# MCU_and_Output_Connectors.net
KiCad netlist of a schematic drawn in Altium Designer
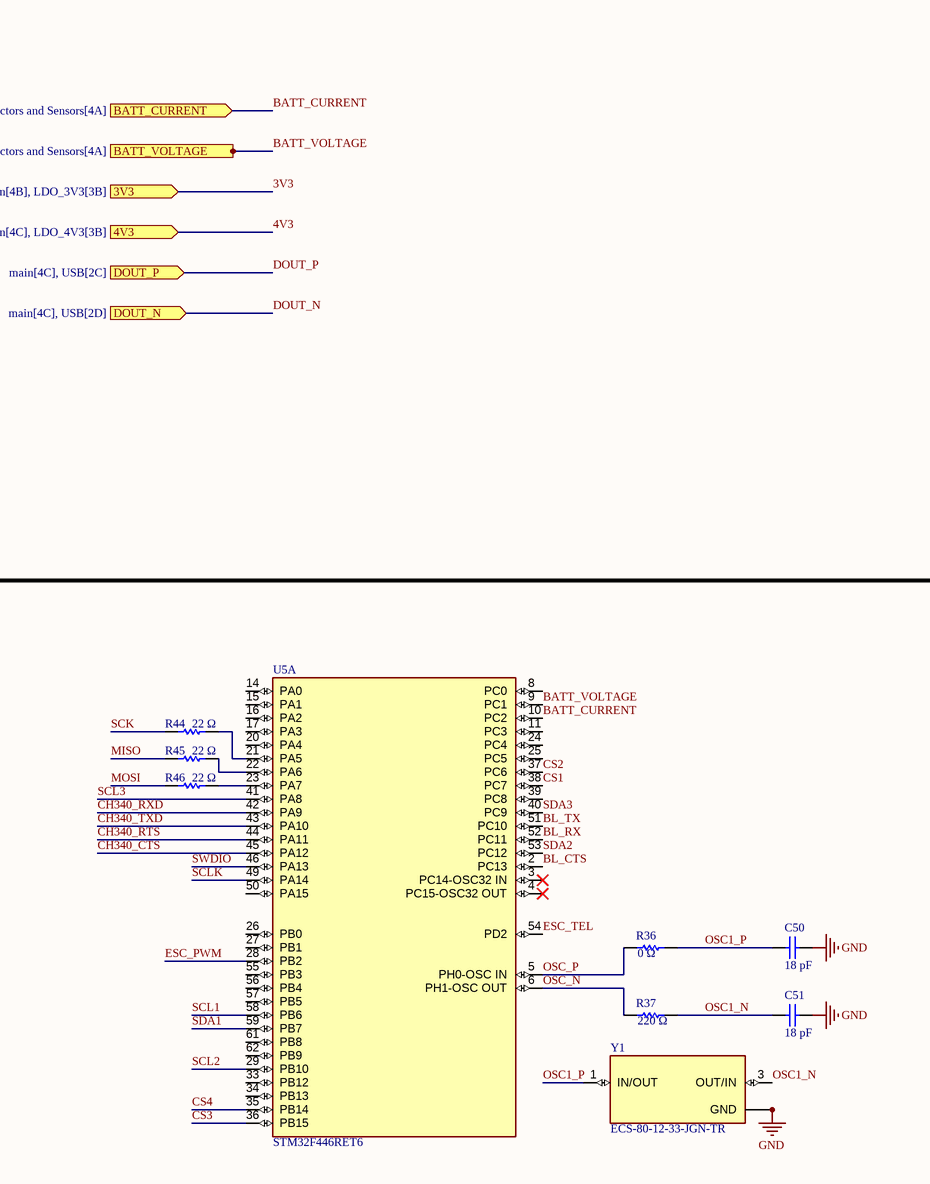
[diagram p0: MCU and Output Connectors.SchDoc, top left]
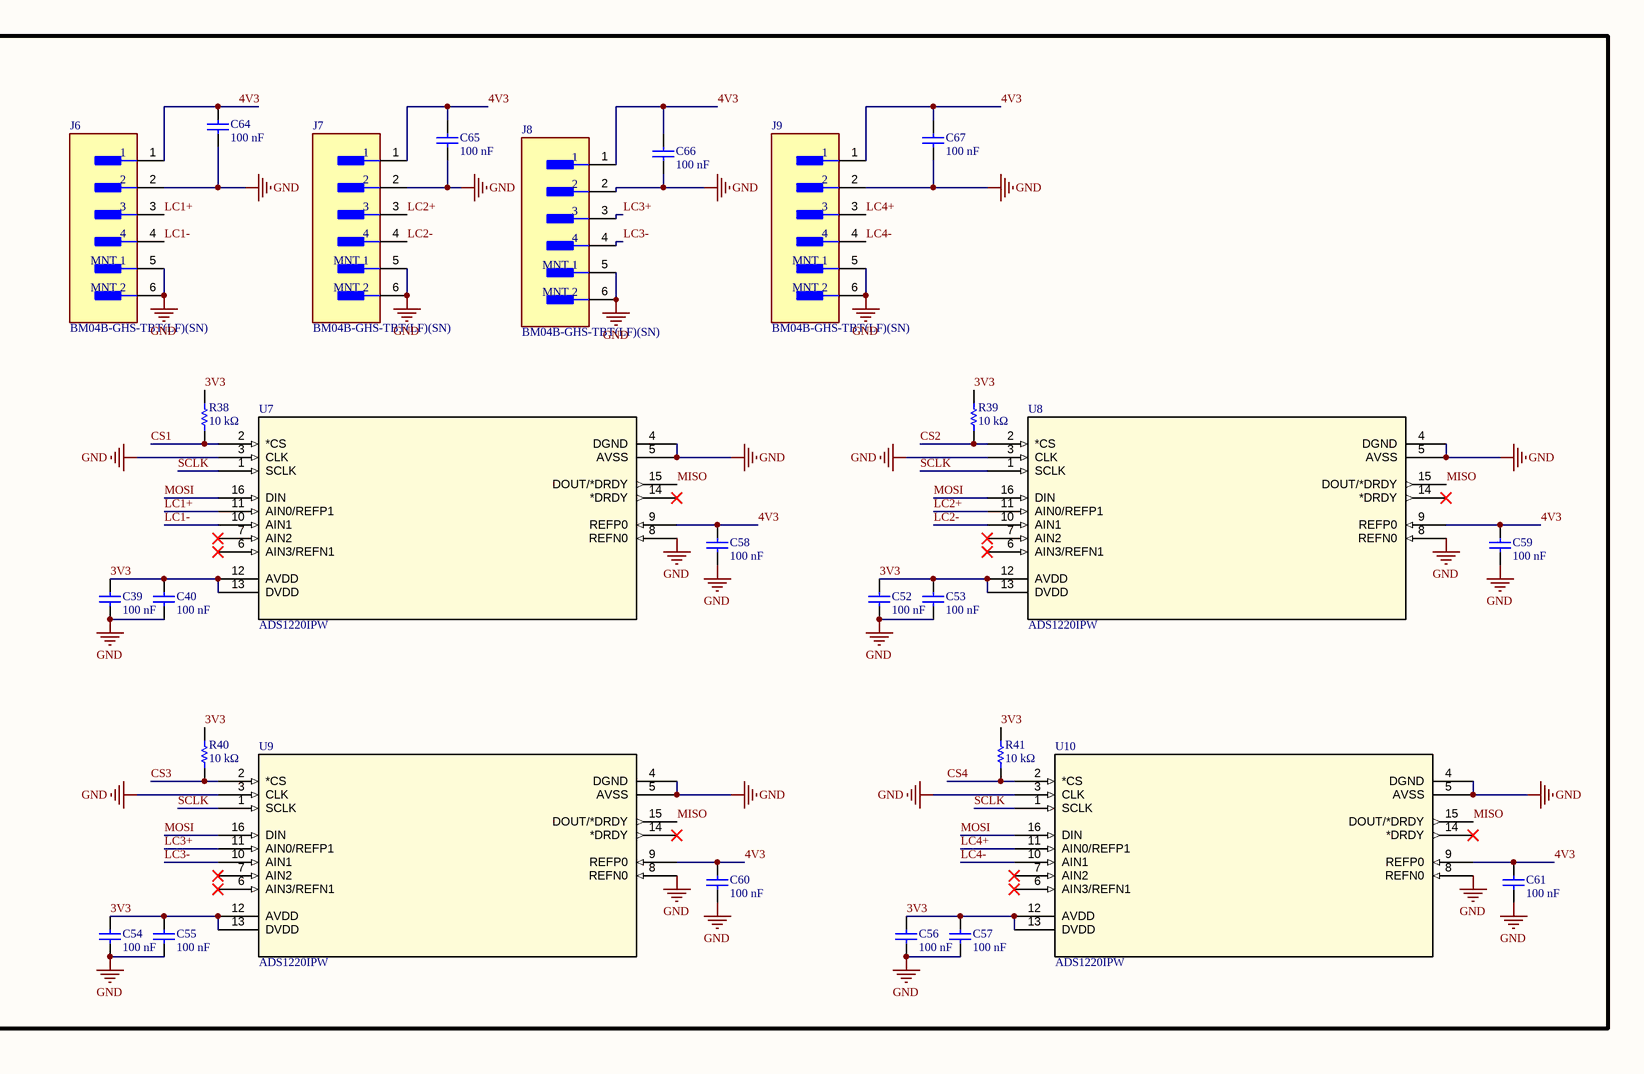
[diagram p1: MCU and Output Connectors.SchDoc, top right]
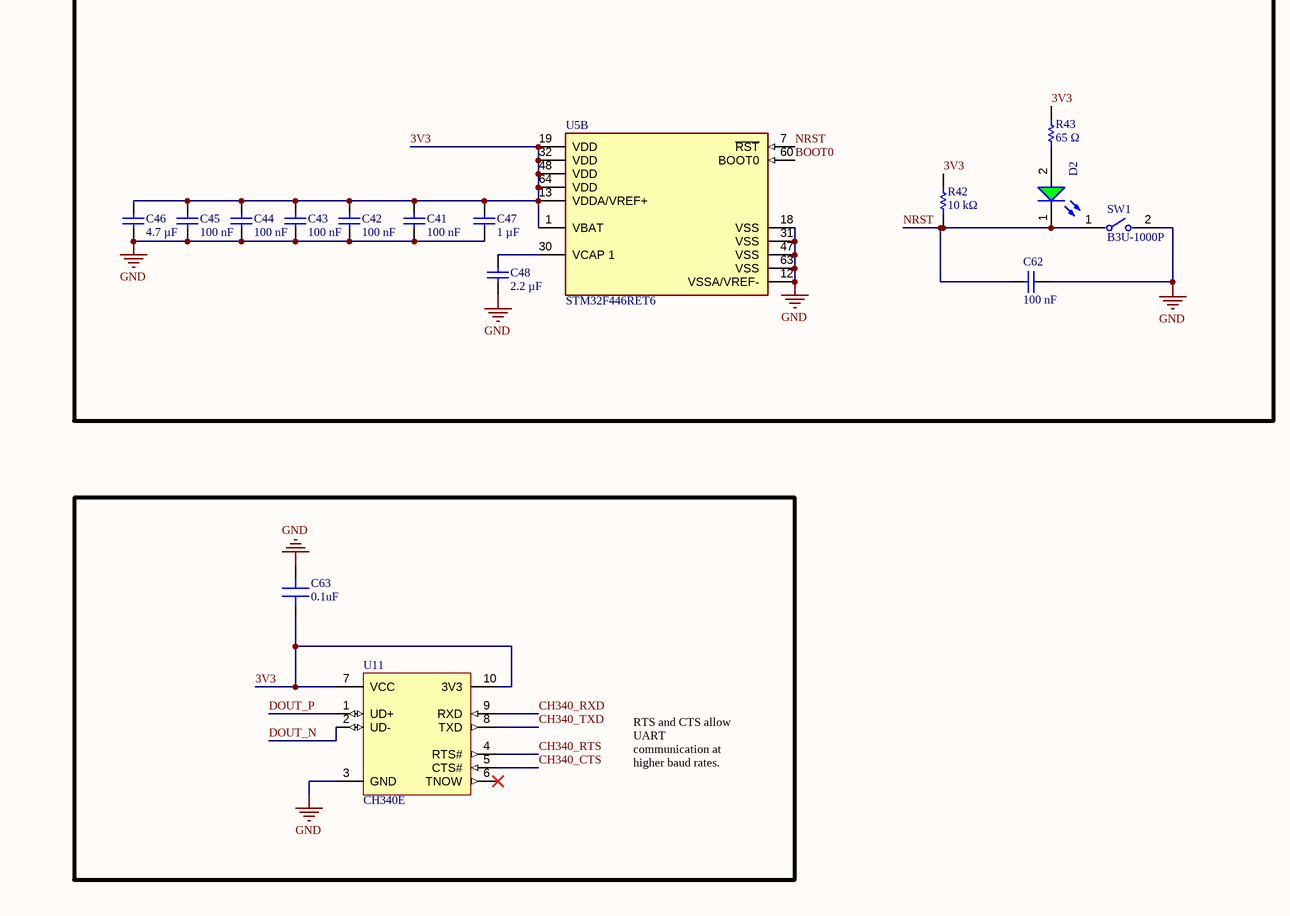
[diagram p2: MCU and Output Connectors.SchDoc, bottom left]
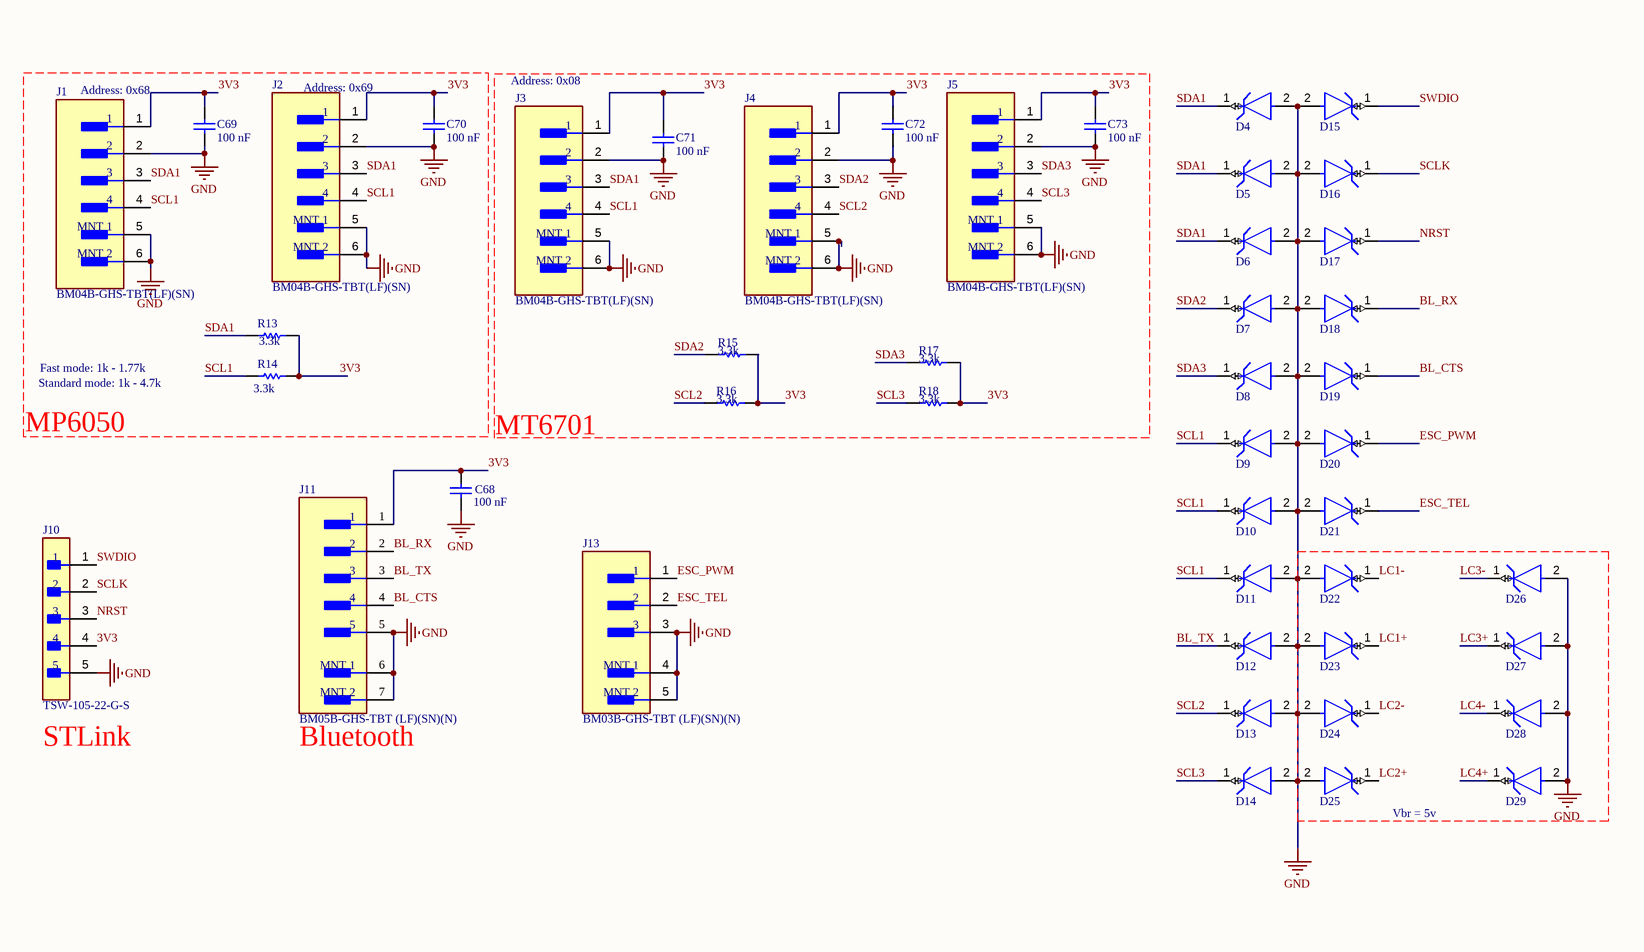
[diagram p3: MCU and Output Connectors.SchDoc, bottom right]

(export (version "E")
  (design (tool "Eeschema 10.0.6"))
  (components
    (comp (ref "C39")
      (value "100 nF")
      (footprint "0402_CAPC1005L")
      (description "Capacitor (Semiconductor SIM Model)")
      (fields (field (name "Comment") "Cap Semi") (field (name "PUBLISHER") "Altium Limited"))
      (libsource (lib "MiscDev 3") (part "Cap Semi"))
    )
    (comp (ref "C40")
      (value "100 nF")
      (footprint "0402_CAPC1005L")
      (description "Capacitor (Semiconductor SIM Model)")
      (fields (field (name "Comment") "Cap Semi") (field (name "PUBLISHER") "Altium Limited"))
      (libsource (lib "MiscDev 3") (part "Cap Semi"))
    )
    (comp (ref "C41")
      (value "100 nF")
      (footprint "0402_CAPC1005L")
      (description "Capacitor (Semiconductor SIM Model)")
      (fields (field (name "Comment") "Cap Semi") (field (name "PUBLISHER") "Altium Limited"))
      (libsource (lib "MiscDev 3") (part "Cap Semi"))
    )
    (comp (ref "C42")
      (value "100 nF")
      (footprint "0402_CAPC1005L")
      (description "Capacitor (Semiconductor SIM Model)")
      (fields (field (name "Comment") "Cap Semi") (field (name "PUBLISHER") "Altium Limited"))
      (libsource (lib "MiscDev 3") (part "Cap Semi"))
    )
    (comp (ref "C43")
      (value "100 nF")
      (footprint "0402_CAPC1005L")
      (description "Capacitor (Semiconductor SIM Model)")
      (fields (field (name "Comment") "Cap Semi") (field (name "PUBLISHER") "Altium Limited"))
      (libsource (lib "MiscDev 3") (part "Cap Semi"))
    )
    (comp (ref "C44")
      (value "100 nF")
      (footprint "0402_CAPC1005L")
      (description "Capacitor (Semiconductor SIM Model)")
      (fields (field (name "Comment") "Cap Semi") (field (name "PUBLISHER") "Altium Limited"))
      (libsource (lib "MiscDev 3") (part "Cap Semi"))
    )
    (comp (ref "C45")
      (value "100 nF")
      (footprint "0402_CAPC1005L")
      (description "Capacitor (Semiconductor SIM Model)")
      (fields (field (name "Comment") "Cap Semi") (field (name "PUBLISHER") "Altium Limited"))
      (libsource (lib "MiscDev 3") (part "Cap Semi"))
    )
    (comp (ref "C46")
      (value "4.7 µF")
      (footprint "0402_CAPC1005L")
      (description "Capacitor (Semiconductor SIM Model)")
      (fields (field (name "Comment") "Cap Semi") (field (name "PUBLISHER") "Altium Limited"))
      (libsource (lib "MiscDev 3") (part "Cap Semi"))
    )
    (comp (ref "C47")
      (value "1 µF")
      (footprint "0402_CAPC1005L")
      (description "Capacitor (Semiconductor SIM Model)")
      (fields (field (name "Comment") "Cap Semi") (field (name "PUBLISHER") "Altium Limited"))
      (libsource (lib "MiscDev 3") (part "Cap Semi"))
    )
    (comp (ref "C48")
      (value "2.2 µF")
      (footprint "0402_CAPC1005L")
      (description "Capacitor (Semiconductor SIM Model)")
      (fields (field (name "Comment") "Cap Semi") (field (name "PUBLISHER") "Altium Limited"))
      (libsource (lib "MiscDev 3") (part "Cap Semi"))
    )
    (comp (ref "C50")
      (value "18 pF")
      (footprint "0402_CAPC1005L")
      (description "Capacitor (Semiconductor SIM Model)")
      (fields (field (name "Comment") "Cap Semi") (field (name "PUBLISHER") "Altium Limited"))
      (libsource (lib "MiscDev 3") (part "Cap Semi"))
    )
    (comp (ref "C51")
      (value "18 pF")
      (footprint "0402_CAPC1005L")
      (description "Capacitor (Semiconductor SIM Model)")
      (fields (field (name "Comment") "Cap Semi") (field (name "PUBLISHER") "Altium Limited"))
      (libsource (lib "MiscDev 3") (part "Cap Semi"))
    )
    (comp (ref "C52")
      (value "100 nF")
      (footprint "0402_CAPC1005L")
      (description "Capacitor (Semiconductor SIM Model)")
      (fields (field (name "Comment") "Cap Semi") (field (name "PUBLISHER") "Altium Limited"))
      (libsource (lib "MiscDev 3") (part "Cap Semi"))
    )
    (comp (ref "C53")
      (value "100 nF")
      (footprint "0402_CAPC1005L")
      (description "Capacitor (Semiconductor SIM Model)")
      (fields (field (name "Comment") "Cap Semi") (field (name "PUBLISHER") "Altium Limited"))
      (libsource (lib "MiscDev 3") (part "Cap Semi"))
    )
    (comp (ref "C54")
      (value "100 nF")
      (footprint "0402_CAPC1005L")
      (description "Capacitor (Semiconductor SIM Model)")
      (fields (field (name "Comment") "Cap Semi") (field (name "PUBLISHER") "Altium Limited"))
      (libsource (lib "MiscDev 3") (part "Cap Semi"))
    )
    (comp (ref "C55")
      (value "100 nF")
      (footprint "0402_CAPC1005L")
      (description "Capacitor (Semiconductor SIM Model)")
      (fields (field (name "Comment") "Cap Semi") (field (name "PUBLISHER") "Altium Limited"))
      (libsource (lib "MiscDev 3") (part "Cap Semi"))
    )
    (comp (ref "C56")
      (value "100 nF")
      (footprint "0402_CAPC1005L")
      (description "Capacitor (Semiconductor SIM Model)")
      (fields (field (name "Comment") "Cap Semi") (field (name "PUBLISHER") "Altium Limited"))
      (libsource (lib "MiscDev 3") (part "Cap Semi"))
    )
    (comp (ref "C57")
      (value "100 nF")
      (footprint "0402_CAPC1005L")
      (description "Capacitor (Semiconductor SIM Model)")
      (fields (field (name "Comment") "Cap Semi") (field (name "PUBLISHER") "Altium Limited"))
      (libsource (lib "MiscDev 3") (part "Cap Semi"))
    )
    (comp (ref "C58")
      (value "100 nF")
      (footprint "0402_CAPC1005L")
      (description "Capacitor (Semiconductor SIM Model)")
      (fields (field (name "Comment") "Cap Semi") (field (name "PUBLISHER") "Altium Limited"))
      (libsource (lib "MiscDev 3") (part "Cap Semi"))
    )
    (comp (ref "C59")
      (value "100 nF")
      (footprint "0402_CAPC1005L")
      (description "Capacitor (Semiconductor SIM Model)")
      (fields (field (name "Comment") "Cap Semi") (field (name "PUBLISHER") "Altium Limited"))
      (libsource (lib "MiscDev 3") (part "Cap Semi"))
    )
    (comp (ref "C60")
      (value "100 nF")
      (footprint "0402_CAPC1005L")
      (description "Capacitor (Semiconductor SIM Model)")
      (fields (field (name "Comment") "Cap Semi") (field (name "PUBLISHER") "Altium Limited"))
      (libsource (lib "MiscDev 3") (part "Cap Semi"))
    )
    (comp (ref "C61")
      (value "100 nF")
      (footprint "0402_CAPC1005L")
      (description "Capacitor (Semiconductor SIM Model)")
      (fields (field (name "Comment") "Cap Semi") (field (name "PUBLISHER") "Altium Limited"))
      (libsource (lib "MiscDev 3") (part "Cap Semi"))
    )
    (comp (ref "C62")
      (value "100 nF")
      (footprint "0402_CAPC1005L")
      (description "Capacitor (Semiconductor SIM Model)")
      (fields (field (name "PUBLISHER") "Altium Limited"))
      (libsource (lib "MiscDev 3") (part "Cap Semi"))
    )
    (comp (ref "C63")
      (value "0.1uF")
      (footprint "IPC C C0402 NO SILK")
      (description "Generic CAP 0402")
      (libsource (lib "University of British Columbia") (part "Generic CAP 1210"))
    )
    (comp (ref "C64")
      (value "100 nF")
      (footprint "0402_CAPC1005L")
      (description "Capacitor (Semiconductor SIM Model)")
      (fields (field (name "Comment") "Cap Semi") (field (name "PUBLISHER") "Altium Limited"))
      (libsource (lib "MiscDev 3") (part "Cap Semi"))
    )
    (comp (ref "C65")
      (value "100 nF")
      (footprint "0402_CAPC1005L")
      (description "Capacitor (Semiconductor SIM Model)")
      (fields (field (name "Comment") "Cap Semi") (field (name "PUBLISHER") "Altium Limited"))
      (libsource (lib "MiscDev 3") (part "Cap Semi"))
    )
    (comp (ref "C66")
      (value "100 nF")
      (footprint "0402_CAPC1005L")
      (description "Capacitor (Semiconductor SIM Model)")
      (fields (field (name "Comment") "Cap Semi") (field (name "PUBLISHER") "Altium Limited"))
      (libsource (lib "MiscDev 3") (part "Cap Semi"))
    )
    (comp (ref "C67")
      (value "100 nF")
      (footprint "0402_CAPC1005L")
      (description "Capacitor (Semiconductor SIM Model)")
      (fields (field (name "Comment") "Cap Semi") (field (name "PUBLISHER") "Altium Limited"))
      (libsource (lib "MiscDev 3") (part "Cap Semi"))
    )
    (comp (ref "C68")
      (value "100 nF")
      (footprint "0402_CAPC1005L")
      (description "Capacitor (Semiconductor SIM Model)")
      (fields (field (name "Comment") "Cap Semi") (field (name "PUBLISHER") "Altium Limited"))
      (libsource (lib "MiscDev 3") (part "Cap Semi"))
    )
    (comp (ref "C69")
      (value "100 nF")
      (footprint "0402_CAPC1005L")
      (description "Capacitor (Semiconductor SIM Model)")
      (fields (field (name "Comment") "Cap Semi") (field (name "PUBLISHER") "Altium Limited"))
      (libsource (lib "MiscDev 3") (part "Cap Semi"))
    )
    (comp (ref "C70")
      (value "100 nF")
      (footprint "0402_CAPC1005L")
      (description "Capacitor (Semiconductor SIM Model)")
      (fields (field (name "Comment") "Cap Semi") (field (name "PUBLISHER") "Altium Limited"))
      (libsource (lib "MiscDev 3") (part "Cap Semi"))
    )
    (comp (ref "C71")
      (value "100 nF")
      (footprint "0402_CAPC1005L")
      (description "Capacitor (Semiconductor SIM Model)")
      (fields (field (name "Comment") "Cap Semi") (field (name "PUBLISHER") "Altium Limited"))
      (libsource (lib "MiscDev 3") (part "Cap Semi"))
    )
    (comp (ref "C72")
      (value "100 nF")
      (footprint "0402_CAPC1005L")
      (description "Capacitor (Semiconductor SIM Model)")
      (fields (field (name "Comment") "Cap Semi") (field (name "PUBLISHER") "Altium Limited"))
      (libsource (lib "MiscDev 3") (part "Cap Semi"))
    )
    (comp (ref "C73")
      (value "100 nF")
      (footprint "0402_CAPC1005L")
      (description "Capacitor (Semiconductor SIM Model)")
      (fields (field (name "Comment") "Cap Semi") (field (name "PUBLISHER") "Altium Limited"))
      (libsource (lib "MiscDev 3") (part "Cap Semi"))
    )
    (comp (ref "D2")
      (value "150060VS75000")
      (footprint "WL-SMCW_0603_150060xx75000")
      (description "LED Uni-Color Green 572nm 2-Pin Chip 0603(1608Metric) T/R")
      (libsource (lib "Altium Content Vault") (part "LED_Green_2A-1K"))
    )
    (comp (ref "D4")
      (value "ESD321DPYR")
      (footprint "FP-DPY0002A-MFG")
      (description "HDMI2.0 ESD PROTECTION")
      (fields
        (field (name "OCTOPART") "https://octopart.com/esd321dpyr-texas+instruments-94354200")
        (field (name "MANUFACTURER") "Texas Instruments")
      )
      (libsource (lib "Altium Content Vault") (part "66ee42db3b8e3650e8893baa18e0b41"))
    )
    (comp (ref "D5")
      (value "ESD321DPYR")
      (footprint "FP-DPY0002A-MFG")
      (description "HDMI2.0 ESD PROTECTION")
      (fields
        (field (name "OCTOPART") "https://octopart.com/esd321dpyr-texas+instruments-94354200")
        (field (name "MANUFACTURER") "Texas Instruments")
      )
      (libsource (lib "Altium Content Vault") (part "66ee42db3b8e3650e8893baa18e0b41"))
    )
    (comp (ref "D6")
      (value "ESD321DPYR")
      (footprint "FP-DPY0002A-MFG")
      (description "HDMI2.0 ESD PROTECTION")
      (fields
        (field (name "OCTOPART") "https://octopart.com/esd321dpyr-texas+instruments-94354200")
        (field (name "MANUFACTURER") "Texas Instruments")
      )
      (libsource (lib "Altium Content Vault") (part "66ee42db3b8e3650e8893baa18e0b41"))
    )
    (comp (ref "D7")
      (value "ESD321DPYR")
      (footprint "FP-DPY0002A-MFG")
      (description "HDMI2.0 ESD PROTECTION")
      (fields
        (field (name "OCTOPART") "https://octopart.com/esd321dpyr-texas+instruments-94354200")
        (field (name "MANUFACTURER") "Texas Instruments")
      )
      (libsource (lib "Altium Content Vault") (part "66ee42db3b8e3650e8893baa18e0b41"))
    )
    (comp (ref "D8")
      (value "ESD321DPYR")
      (footprint "FP-DPY0002A-MFG")
      (description "HDMI2.0 ESD PROTECTION")
      (fields
        (field (name "OCTOPART") "https://octopart.com/esd321dpyr-texas+instruments-94354200")
        (field (name "MANUFACTURER") "Texas Instruments")
      )
      (libsource (lib "Altium Content Vault") (part "66ee42db3b8e3650e8893baa18e0b41"))
    )
    (comp (ref "D9")
      (value "ESD321DPYR")
      (footprint "FP-DPY0002A-MFG")
      (description "HDMI2.0 ESD PROTECTION")
      (fields
        (field (name "OCTOPART") "https://octopart.com/esd321dpyr-texas+instruments-94354200")
        (field (name "MANUFACTURER") "Texas Instruments")
      )
      (libsource (lib "Altium Content Vault") (part "66ee42db3b8e3650e8893baa18e0b41"))
    )
    (comp (ref "D10")
      (value "ESD321DPYR")
      (footprint "FP-DPY0002A-MFG")
      (description "HDMI2.0 ESD PROTECTION")
      (fields
        (field (name "OCTOPART") "https://octopart.com/esd321dpyr-texas+instruments-94354200")
        (field (name "MANUFACTURER") "Texas Instruments")
      )
      (libsource (lib "Altium Content Vault") (part "66ee42db3b8e3650e8893baa18e0b41"))
    )
    (comp (ref "D11")
      (value "ESD321DPYR")
      (footprint "FP-DPY0002A-MFG")
      (description "HDMI2.0 ESD PROTECTION")
      (fields
        (field (name "OCTOPART") "https://octopart.com/esd321dpyr-texas+instruments-94354200")
        (field (name "MANUFACTURER") "Texas Instruments")
      )
      (libsource (lib "Altium Content Vault") (part "66ee42db3b8e3650e8893baa18e0b41"))
    )
    (comp (ref "D12")
      (value "ESD321DPYR")
      (footprint "FP-DPY0002A-MFG")
      (description "HDMI2.0 ESD PROTECTION")
      (fields
        (field (name "OCTOPART") "https://octopart.com/esd321dpyr-texas+instruments-94354200")
        (field (name "MANUFACTURER") "Texas Instruments")
      )
      (libsource (lib "Altium Content Vault") (part "66ee42db3b8e3650e8893baa18e0b41"))
    )
    (comp (ref "D13")
      (value "ESD321DPYR")
      (footprint "FP-DPY0002A-MFG")
      (description "HDMI2.0 ESD PROTECTION")
      (fields
        (field (name "OCTOPART") "https://octopart.com/esd321dpyr-texas+instruments-94354200")
        (field (name "MANUFACTURER") "Texas Instruments")
      )
      (libsource (lib "Altium Content Vault") (part "66ee42db3b8e3650e8893baa18e0b41"))
    )
    (comp (ref "D14")
      (value "ESD321DPYR")
      (footprint "FP-DPY0002A-MFG")
      (description "HDMI2.0 ESD PROTECTION")
      (fields
        (field (name "OCTOPART") "https://octopart.com/esd321dpyr-texas+instruments-94354200")
        (field (name "MANUFACTURER") "Texas Instruments")
      )
      (libsource (lib "Altium Content Vault") (part "66ee42db3b8e3650e8893baa18e0b41"))
    )
    (comp (ref "D15")
      (value "ESD321DPYR")
      (footprint "FP-DPY0002A-MFG")
      (description "HDMI2.0 ESD PROTECTION")
      (fields
        (field (name "OCTOPART") "https://octopart.com/esd321dpyr-texas+instruments-94354200")
        (field (name "MANUFACTURER") "Texas Instruments")
      )
      (libsource (lib "Altium Content Vault") (part "66ee42db3b8e3650e8893baa18e0b41"))
    )
    (comp (ref "D16")
      (value "ESD321DPYR")
      (footprint "FP-DPY0002A-MFG")
      (description "HDMI2.0 ESD PROTECTION")
      (fields
        (field (name "OCTOPART") "https://octopart.com/esd321dpyr-texas+instruments-94354200")
        (field (name "MANUFACTURER") "Texas Instruments")
      )
      (libsource (lib "Altium Content Vault") (part "66ee42db3b8e3650e8893baa18e0b41"))
    )
    (comp (ref "D17")
      (value "ESD321DPYR")
      (footprint "FP-DPY0002A-MFG")
      (description "HDMI2.0 ESD PROTECTION")
      (fields
        (field (name "OCTOPART") "https://octopart.com/esd321dpyr-texas+instruments-94354200")
        (field (name "MANUFACTURER") "Texas Instruments")
      )
      (libsource (lib "Altium Content Vault") (part "66ee42db3b8e3650e8893baa18e0b41"))
    )
    (comp (ref "D18")
      (value "ESD321DPYR")
      (footprint "FP-DPY0002A-MFG")
      (description "HDMI2.0 ESD PROTECTION")
      (fields
        (field (name "OCTOPART") "https://octopart.com/esd321dpyr-texas+instruments-94354200")
        (field (name "MANUFACTURER") "Texas Instruments")
      )
      (libsource (lib "Altium Content Vault") (part "66ee42db3b8e3650e8893baa18e0b41"))
    )
    (comp (ref "D19")
      (value "ESD321DPYR")
      (footprint "FP-DPY0002A-MFG")
      (description "HDMI2.0 ESD PROTECTION")
      (fields
        (field (name "OCTOPART") "https://octopart.com/esd321dpyr-texas+instruments-94354200")
        (field (name "MANUFACTURER") "Texas Instruments")
      )
      (libsource (lib "Altium Content Vault") (part "66ee42db3b8e3650e8893baa18e0b41"))
    )
    (comp (ref "D20")
      (value "ESD321DPYR")
      (footprint "FP-DPY0002A-MFG")
      (description "HDMI2.0 ESD PROTECTION")
      (fields
        (field (name "OCTOPART") "https://octopart.com/esd321dpyr-texas+instruments-94354200")
        (field (name "MANUFACTURER") "Texas Instruments")
      )
      (libsource (lib "Altium Content Vault") (part "66ee42db3b8e3650e8893baa18e0b41"))
    )
    (comp (ref "D21")
      (value "ESD321DPYR")
      (footprint "FP-DPY0002A-MFG")
      (description "HDMI2.0 ESD PROTECTION")
      (fields
        (field (name "OCTOPART") "https://octopart.com/esd321dpyr-texas+instruments-94354200")
        (field (name "MANUFACTURER") "Texas Instruments")
      )
      (libsource (lib "Altium Content Vault") (part "66ee42db3b8e3650e8893baa18e0b41"))
    )
    (comp (ref "D22")
      (value "SP0402U-ULC-01ETG")
      (footprint "FP-DPY0002A-MFG")
      (description "TVS DIODE 5VWM 9.2VC 0402/2DFN")
      (fields
        (field (name "OCTOPART") "https://octopart.com/esd321dpyr-texas+instruments-94354200")
        (field (name "MANUFACTURER PART NUMBER") "ESD321DPYR")
      )
      (libsource (lib "Altium Content Vault") (part "66ee42db3b8e3650e8893baa18e0b41"))
    )
    (comp (ref "D23")
      (value "SP0402U-ULC-01ETG")
      (footprint "FP-DPY0002A-MFG")
      (description "TVS DIODE 5VWM 9.2VC 0402/2DFN")
      (fields
        (field (name "OCTOPART") "https://octopart.com/esd321dpyr-texas+instruments-94354200")
        (field (name "MANUFACTURER PART NUMBER") "ESD321DPYR")
      )
      (libsource (lib "Altium Content Vault") (part "66ee42db3b8e3650e8893baa18e0b41"))
    )
    (comp (ref "D24")
      (value "SP0402U-ULC-01ETG")
      (footprint "FP-DPY0002A-MFG")
      (description "TVS DIODE 5VWM 9.2VC 0402/2DFN")
      (fields
        (field (name "OCTOPART") "https://octopart.com/esd321dpyr-texas+instruments-94354200")
        (field (name "MANUFACTURER PART NUMBER") "ESD321DPYR")
      )
      (libsource (lib "Altium Content Vault") (part "66ee42db3b8e3650e8893baa18e0b41"))
    )
    (comp (ref "D25")
      (value "SP0402U-ULC-01ETG")
      (footprint "FP-DPY0002A-MFG")
      (description "TVS DIODE 5VWM 9.2VC 0402/2DFN")
      (fields
        (field (name "OCTOPART") "https://octopart.com/esd321dpyr-texas+instruments-94354200")
        (field (name "MANUFACTURER PART NUMBER") "ESD321DPYR")
      )
      (libsource (lib "Altium Content Vault") (part "66ee42db3b8e3650e8893baa18e0b41"))
    )
    (comp (ref "D26")
      (value "SP0402U-ULC-01ETG")
      (footprint "FP-DPY0002A-MFG")
      (description "TVS DIODE 5VWM 9.2VC 0402/2DFN")
      (fields
        (field (name "OCTOPART") "https://octopart.com/esd321dpyr-texas+instruments-94354200")
        (field (name "MANUFACTURER PART NUMBER") "ESD321DPYR")
      )
      (libsource (lib "Altium Content Vault") (part "66ee42db3b8e3650e8893baa18e0b41"))
    )
    (comp (ref "D27")
      (value "SP0402U-ULC-01ETG")
      (footprint "FP-DPY0002A-MFG")
      (description "TVS DIODE 5VWM 9.2VC 0402/2DFN")
      (fields
        (field (name "OCTOPART") "https://octopart.com/esd321dpyr-texas+instruments-94354200")
        (field (name "MANUFACTURER PART NUMBER") "ESD321DPYR")
      )
      (libsource (lib "Altium Content Vault") (part "66ee42db3b8e3650e8893baa18e0b41"))
    )
    (comp (ref "D28")
      (value "SP0402U-ULC-01ETG")
      (footprint "FP-DPY0002A-MFG")
      (description "TVS DIODE 5VWM 9.2VC 0402/2DFN")
      (fields
        (field (name "OCTOPART") "https://octopart.com/esd321dpyr-texas+instruments-94354200")
        (field (name "MANUFACTURER PART NUMBER") "ESD321DPYR")
      )
      (libsource (lib "Altium Content Vault") (part "66ee42db3b8e3650e8893baa18e0b41"))
    )
    (comp (ref "D29")
      (value "SP0402U-ULC-01ETG")
      (footprint "FP-DPY0002A-MFG")
      (description "TVS DIODE 5VWM 9.2VC 0402/2DFN")
      (fields
        (field (name "OCTOPART") "https://octopart.com/esd321dpyr-texas+instruments-94354200")
        (field (name "MANUFACTURER PART NUMBER") "ESD321DPYR")
      )
      (libsource (lib "Altium Content Vault") (part "66ee42db3b8e3650e8893baa18e0b41"))
    )
    (comp (ref "J1")
      (value "BM04B-GHS-TBT(LF)(SN)")
      (footprint "FP-BM04B-GHS-TBT_LF_SN-MFG")
      (description "CONN HEADER SMD 4POS 1.25MM")
      (libsource (lib "Altium Content Vault") (part "8e3688c4b118bffc0dd9b7401e414ba"))
    )
    (comp (ref "J2")
      (value "BM04B-GHS-TBT(LF)(SN)")
      (footprint "FP-BM04B-GHS-TBT_LF_SN-MFG")
      (description "CONN HEADER SMD 4POS 1.25MM")
      (libsource (lib "Altium Content Vault") (part "8e3688c4b118bffc0dd9b7401e414ba"))
    )
    (comp (ref "J3")
      (value "BM04B-GHS-TBT(LF)(SN)")
      (footprint "FP-BM04B-GHS-TBT_LF_SN-MFG")
      (description "CONN HEADER SMD 4POS 1.25MM")
      (libsource (lib "Altium Content Vault") (part "8e3688c4b118bffc0dd9b7401e414ba"))
    )
    (comp (ref "J4")
      (value "BM04B-GHS-TBT(LF)(SN)")
      (footprint "FP-BM04B-GHS-TBT_LF_SN-MFG")
      (description "CONN HEADER SMD 4POS 1.25MM")
      (libsource (lib "Altium Content Vault") (part "8e3688c4b118bffc0dd9b7401e414ba"))
    )
    (comp (ref "J5")
      (value "BM04B-GHS-TBT(LF)(SN)")
      (footprint "FP-BM04B-GHS-TBT_LF_SN-MFG")
      (description "CONN HEADER SMD 4POS 1.25MM")
      (libsource (lib "Altium Content Vault") (part "8e3688c4b118bffc0dd9b7401e414ba"))
    )
    (comp (ref "J6")
      (value "BM04B-GHS-TBT(LF)(SN)")
      (footprint "FP-BM04B-GHS-TBT_LF_SN-MFG")
      (description "CONN HEADER SMD 4POS 1.25MM")
      (libsource (lib "Altium Content Vault") (part "8e3688c4b118bffc0dd9b7401e414ba"))
    )
    (comp (ref "J7")
      (value "BM04B-GHS-TBT(LF)(SN)")
      (footprint "FP-BM04B-GHS-TBT_LF_SN-MFG")
      (description "CONN HEADER SMD 4POS 1.25MM")
      (libsource (lib "Altium Content Vault") (part "8e3688c4b118bffc0dd9b7401e414ba"))
    )
    (comp (ref "J8")
      (value "BM04B-GHS-TBT(LF)(SN)")
      (footprint "FP-BM04B-GHS-TBT_LF_SN-MFG")
      (description "CONN HEADER SMD 4POS 1.25MM")
      (libsource (lib "Altium Content Vault") (part "8e3688c4b118bffc0dd9b7401e414ba"))
    )
    (comp (ref "J9")
      (value "BM04B-GHS-TBT(LF)(SN)")
      (footprint "FP-BM04B-GHS-TBT_LF_SN-MFG")
      (description "CONN HEADER SMD 4POS 1.25MM")
      (libsource (lib "Altium Content Vault") (part "8e3688c4b118bffc0dd9b7401e414ba"))
    )
    (comp (ref "J10")
      (value "TSW-105-22-G-S")
      (footprint "FP-TSW-105-22-G-S-MFG")
      (description "CONN HEADER VERT 5POS 2.54MM")
      (libsource (lib "Altium Content Vault") (part "bf93c07fd2649a848d0ec8585582aab"))
    )
    (comp (ref "J11")
      (value "BM05B-GHS-TBT (LF)(SN)(N)")
      (footprint "FP-BM05B-GHS-TBT_LF_SN-MFG")
      (description "CONN HEADER SMD 5POS 1.25MM")
      (libsource (lib "Altium Content Vault") (part "a8463467369b6bfccc80258e24cb490"))
    )
    (comp (ref "J13")
      (value "BM03B-GHS-TBT (LF)(SN)(N)")
      (footprint "FP-BM03B-GHS-TBT_LF_SN-MFG")
      (description "CONN HEADER SMD 3POS 1.25MM")
      (libsource (lib "Altium Content Vault") (part "13850a6865a90496d8e6d51657cef87"))
    )
    (comp (ref "R13")
      (value "3.3k")
      (footprint "0402_RESC1005L")
      (description "Semiconductor Resistor")
      (fields (field (name "Comment") "Res Semi") (field (name "PUBLISHER") "Altium Limited"))
      (libsource (lib "MiscDev 3") (part "Res Semi"))
    )
    (comp (ref "R14")
      (value "3.3k")
      (footprint "0402_RESC1005L")
      (description "Semiconductor Resistor")
      (fields (field (name "Comment") "Res Semi") (field (name "PUBLISHER") "Altium Limited"))
      (libsource (lib "MiscDev 3") (part "Res Semi"))
    )
    (comp (ref "R15")
      (value "3.3k")
      (footprint "0402_RESC1005L")
      (description "Semiconductor Resistor")
      (fields (field (name "Comment") "Res Semi") (field (name "PUBLISHER") "Altium Limited"))
      (libsource (lib "MiscDev 3") (part "Res Semi"))
    )
    (comp (ref "R16")
      (value "3.3k")
      (footprint "0402_RESC1005L")
      (description "Semiconductor Resistor")
      (fields (field (name "Comment") "Res Semi") (field (name "PUBLISHER") "Altium Limited"))
      (libsource (lib "MiscDev 3") (part "Res Semi"))
    )
    (comp (ref "R17")
      (value "3.3k")
      (footprint "0402_RESC1005L")
      (description "Semiconductor Resistor")
      (fields (field (name "Comment") "Res Semi") (field (name "PUBLISHER") "Altium Limited"))
      (libsource (lib "MiscDev 3") (part "Res Semi"))
    )
    (comp (ref "R18")
      (value "3.3k")
      (footprint "0402_RESC1005L")
      (description "Semiconductor Resistor")
      (fields (field (name "Comment") "Res Semi") (field (name "PUBLISHER") "Altium Limited"))
      (libsource (lib "MiscDev 3") (part "Res Semi"))
    )
    (comp (ref "R36")
      (value "0 Ω")
      (footprint "0402_RESC1005L")
      (description "Semiconductor Resistor")
      (fields (field (name "Comment") "Res Semi") (field (name "PUBLISHER") "Altium Limited"))
      (libsource (lib "MiscDev 3") (part "Res Semi"))
    )
    (comp (ref "R37")
      (value "220 Ω")
      (footprint "0402_RESC1005L")
      (description "Semiconductor Resistor")
      (fields (field (name "Comment") "Res Semi") (field (name "PUBLISHER") "Altium Limited"))
      (libsource (lib "MiscDev 3") (part "Res Semi"))
    )
    (comp (ref "R38")
      (value "10 kΩ")
      (footprint "0402_RESC1005L")
      (description "Semiconductor Resistor")
      (fields (field (name "Comment") "Res Semi") (field (name "PUBLISHER") "Altium Limited"))
      (libsource (lib "MiscDev 3") (part "Res Semi"))
    )
    (comp (ref "R39")
      (value "10 kΩ")
      (footprint "0402_RESC1005L")
      (description "Semiconductor Resistor")
      (fields (field (name "Comment") "Res Semi") (field (name "PUBLISHER") "Altium Limited"))
      (libsource (lib "MiscDev 3") (part "Res Semi"))
    )
    (comp (ref "R40")
      (value "10 kΩ")
      (footprint "0402_RESC1005L")
      (description "Semiconductor Resistor")
      (fields (field (name "Comment") "Res Semi") (field (name "PUBLISHER") "Altium Limited"))
      (libsource (lib "MiscDev 3") (part "Res Semi"))
    )
    (comp (ref "R41")
      (value "10 kΩ")
      (footprint "0402_RESC1005L")
      (description "Semiconductor Resistor")
      (fields (field (name "Comment") "Res Semi") (field (name "PUBLISHER") "Altium Limited"))
      (libsource (lib "MiscDev 3") (part "Res Semi"))
    )
    (comp (ref "R42")
      (value "10 kΩ")
      (footprint "0402_RESC1005L")
      (description "Semiconductor Resistor 1%")
      (fields (field (name "Comment") "Res Semi") (field (name "PUBLISHER") "Altium Limited"))
      (libsource (lib "MiscDev 3") (part "Res Semi"))
    )
    (comp (ref "R43")
      (value "65 Ω")
      (footprint "0603_RESC1608L")
      (description "Semiconductor Resistor")
      (fields (field (name "Comment") "Res Semi") (field (name "PUBLISHER") "Altium Limited"))
      (libsource (lib "MiscDev 3") (part "Res Semi"))
    )
    (comp (ref "R44")
      (value "22 Ω")
      (footprint "0402_RESC1005L")
      (description "Semiconductor Resistor 1%")
      (fields (field (name "Comment") "Res Semi") (field (name "PUBLISHER") "Altium Limited"))
      (libsource (lib "MiscDev 3") (part "Res Semi"))
    )
    (comp (ref "R45")
      (value "22 Ω")
      (footprint "0402_RESC1005L")
      (description "Semiconductor Resistor 1%")
      (fields (field (name "Comment") "Res Semi") (field (name "PUBLISHER") "Altium Limited"))
      (libsource (lib "MiscDev 3") (part "Res Semi"))
    )
    (comp (ref "R46")
      (value "22 Ω")
      (footprint "0402_RESC1005L")
      (description "Semiconductor Resistor 1%")
      (fields (field (name "Comment") "Res Semi") (field (name "PUBLISHER") "Altium Limited"))
      (libsource (lib "MiscDev 3") (part "Res Semi"))
    )
    (comp (ref "SW1")
      (value "B3U-1000P")
      (footprint "FP-B3U-1000P-MFG")
      (description "SWITCH TACTILE SPST-NO 0.05A 12V")
      (libsource (lib "Altium Content Vault") (part "ae622034201233ca1abcedc05908f33"))
    )
    (comp (ref "U5")
      (value "STM32F446RET6")
      (footprint "FP-LQFP64-5W-MFG")
      (description "IC MCU 32BIT 512KB FLASH 64LQFP")
      (fields
        (field (name "OCTOPART") "https://octopart.com/stm32f446ret6-stmicroelectronics-52642920")
        (field (name "MANUFACTURER") "ST")
      )
      (libsource (lib "Altium Content Vault") (part "ee11adc32c0ab33b933cccf4348c338"))
    )
    (comp (ref "U7")
      (value "ADS1220IPW")
      (footprint "PW16")
      (fields (field (name "COPYRIGHT") "Copyright (C) 2025 Ultra Librarian. All rights reserved."))
      (libsource (lib "ADS1220IPW") (part "ADS1220IPW"))
    )
    (comp (ref "U8")
      (value "ADS1220IPW")
      (footprint "PW16")
      (fields (field (name "COPYRIGHT") "Copyright (C) 2025 Ultra Librarian. All rights reserved."))
      (libsource (lib "ADS1220IPW") (part "ADS1220IPW"))
    )
    (comp (ref "U9")
      (value "ADS1220IPW")
      (footprint "PW16")
      (fields (field (name "COPYRIGHT") "Copyright (C) 2025 Ultra Librarian. All rights reserved."))
      (libsource (lib "ADS1220IPW") (part "ADS1220IPW"))
    )
    (comp (ref "U10")
      (value "ADS1220IPW")
      (footprint "PW16")
      (fields (field (name "COPYRIGHT") "Copyright (C) 2025 Ultra Librarian. All rights reserved."))
      (libsource (lib "ADS1220IPW") (part "ADS1220IPW"))
    )
    (comp (ref "U11")
      (value "CH340E")
      (footprint "MSOP-UN10_L")
      (libsource (lib "University of British Columbia") (part "CH340E"))
    )
    (comp (ref "Y1")
      (value "ECS-80-12-33-JGN-TR")
      (footprint "XTAL_ECS-240-8-33-AGN-TR")
      (description "8 MHz Â±20ppm Crystal 12pF 400 Ohms 4-SMD, No Lead")
      (fields (field (name "MF") "ECS Inc."))
      (libsource (lib "ECS-80-12-33-JGN-TR") (part "ECS-80-12-33-JGN-TR"))
    )
  )
  (nets
    (net (code "1") (name "/3V3") (class "Default")
      (node (ref "C39") (pin "1") (pinfunction "1_1") (pintype "passive"))
      (node (ref "C40") (pin "1") (pinfunction "1_1") (pintype "passive"))
      (node (ref "C41") (pin "1") (pinfunction "1_1") (pintype "passive"))
      (node (ref "C42") (pin "1") (pinfunction "1_1") (pintype "passive"))
      (node (ref "C43") (pin "1") (pinfunction "1_1") (pintype "passive"))
      (node (ref "C44") (pin "1") (pinfunction "1_1") (pintype "passive"))
      (node (ref "C45") (pin "1") (pinfunction "1_1") (pintype "passive"))
      (node (ref "C46") (pin "1") (pinfunction "1_1") (pintype "passive"))
      (node (ref "C47") (pin "1") (pinfunction "1_1") (pintype "passive"))
      (node (ref "C52") (pin "1") (pinfunction "1_1") (pintype "passive"))
      (node (ref "C53") (pin "1") (pinfunction "1_1") (pintype "passive"))
      (node (ref "C54") (pin "1") (pinfunction "1_1") (pintype "passive"))
      (node (ref "C55") (pin "1") (pinfunction "1_1") (pintype "passive"))
      (node (ref "C56") (pin "1") (pinfunction "1_1") (pintype "passive"))
      (node (ref "C57") (pin "1") (pinfunction "1_1") (pintype "passive"))
      (node (ref "C63") (pin "2") (pinfunction "2_2") (pintype "passive"))
      (node (ref "C68") (pin "1") (pinfunction "1_1") (pintype "passive"))
      (node (ref "C69") (pin "1") (pinfunction "1_1") (pintype "passive"))
      (node (ref "C70") (pin "1") (pinfunction "1_1") (pintype "passive"))
      (node (ref "C71") (pin "1") (pinfunction "1_1") (pintype "passive"))
      (node (ref "C72") (pin "1") (pinfunction "1_1") (pintype "passive"))
      (node (ref "C73") (pin "1") (pinfunction "1_1") (pintype "passive"))
      (node (ref "J1") (pin "1") (pinfunction "1_1") (pintype "passive"))
      (node (ref "J10") (pin "4") (pinfunction "4_4") (pintype "passive"))
      (node (ref "J11") (pin "1") (pinfunction "1_1") (pintype "passive"))
      (node (ref "J2") (pin "1") (pinfunction "1_1") (pintype "passive"))
      (node (ref "J3") (pin "1") (pinfunction "1_1") (pintype "passive"))
      (node (ref "J4") (pin "1") (pinfunction "1_1") (pintype "passive"))
      (node (ref "J5") (pin "1") (pinfunction "1_1") (pintype "passive"))
      (node (ref "R13") (pin "2") (pinfunction "2_2") (pintype "passive"))
      (node (ref "R14") (pin "2") (pinfunction "2_2") (pintype "passive"))
      (node (ref "R15") (pin "2") (pinfunction "2_2") (pintype "passive"))
      (node (ref "R16") (pin "2") (pinfunction "2_2") (pintype "passive"))
      (node (ref "R17") (pin "2") (pinfunction "2_2") (pintype "passive"))
      (node (ref "R18") (pin "2") (pinfunction "2_2") (pintype "passive"))
      (node (ref "R38") (pin "2") (pinfunction "2_2") (pintype "passive"))
      (node (ref "R39") (pin "2") (pinfunction "2_2") (pintype "passive"))
      (node (ref "R40") (pin "2") (pinfunction "2_2") (pintype "passive"))
      (node (ref "R41") (pin "2") (pinfunction "2_2") (pintype "passive"))
      (node (ref "R42") (pin "2") (pinfunction "2_2") (pintype "passive"))
      (node (ref "R43") (pin "1") (pinfunction "1_1") (pintype "passive"))
      (node (ref "U10") (pin "12") (pinfunction "AVDD_12") (pintype "power_in"))
      (node (ref "U10") (pin "13") (pinfunction "DVDD_13") (pintype "power_in"))
      (node (ref "U11") (pin "10") (pinfunction "3V3_10") (pintype "power_in"))
      (node (ref "U11") (pin "7") (pinfunction "VCC_7") (pintype "power_in"))
      (node (ref "U5") (pin "1") (pinfunction "VBAT_1") (pintype "power_in"))
      (node (ref "U5") (pin "13") (pinfunction "VDDA/VREF+_13") (pintype "power_in"))
      (node (ref "U5") (pin "19") (pinfunction "VDD_19") (pintype "power_in"))
      (node (ref "U5") (pin "32") (pinfunction "VDD_32") (pintype "power_in"))
      (node (ref "U5") (pin "48") (pinfunction "VDD_48") (pintype "power_in"))
      (node (ref "U5") (pin "64") (pinfunction "VDD_64") (pintype "power_in"))
      (node (ref "U7") (pin "12") (pinfunction "AVDD_12") (pintype "power_in"))
      (node (ref "U7") (pin "13") (pinfunction "DVDD_13") (pintype "power_in"))
      (node (ref "U8") (pin "12") (pinfunction "AVDD_12") (pintype "power_in"))
      (node (ref "U8") (pin "13") (pinfunction "DVDD_13") (pintype "power_in"))
      (node (ref "U9") (pin "12") (pinfunction "AVDD_12") (pintype "power_in"))
      (node (ref "U9") (pin "13") (pinfunction "DVDD_13") (pintype "power_in"))
    )
    (net (code "2") (name "/4V3") (class "Default")
      (node (ref "C58") (pin "1") (pinfunction "1_1") (pintype "passive"))
      (node (ref "C59") (pin "1") (pinfunction "1_1") (pintype "passive"))
      (node (ref "C60") (pin "1") (pinfunction "1_1") (pintype "passive"))
      (node (ref "C61") (pin "1") (pinfunction "1_1") (pintype "passive"))
      (node (ref "C64") (pin "1") (pinfunction "1_1") (pintype "passive"))
      (node (ref "C65") (pin "1") (pinfunction "1_1") (pintype "passive"))
      (node (ref "C66") (pin "1") (pinfunction "1_1") (pintype "passive"))
      (node (ref "C67") (pin "1") (pinfunction "1_1") (pintype "passive"))
      (node (ref "J6") (pin "1") (pinfunction "1_1") (pintype "passive"))
      (node (ref "J7") (pin "1") (pinfunction "1_1") (pintype "passive"))
      (node (ref "J8") (pin "1") (pinfunction "1_1") (pintype "passive"))
      (node (ref "J9") (pin "1") (pinfunction "1_1") (pintype "passive"))
      (node (ref "U10") (pin "9") (pinfunction "REFP0_9") (pintype "input"))
      (node (ref "U7") (pin "9") (pinfunction "REFP0_9") (pintype "input"))
      (node (ref "U8") (pin "9") (pinfunction "REFP0_9") (pintype "input"))
      (node (ref "U9") (pin "9") (pinfunction "REFP0_9") (pintype "input"))
    )
    (net (code "3") (name "/BATT_CURRENT") (class "Default")
      (node (ref "U5") (pin "10") (pinfunction "PC2_10") (pintype "bidirectional"))
    )
    (net (code "4") (name "/BATT_VOLTAGE") (class "Default")
      (node (ref "U5") (pin "9") (pinfunction "PC1_9") (pintype "bidirectional"))
    )
    (net (code "5") (name "/BL_CTS") (class "Default")
      (node (ref "D19") (pin "1") (pinfunction "IO_1") (pintype "bidirectional"))
      (node (ref "J11") (pin "4") (pinfunction "4_4") (pintype "passive"))
      (node (ref "U5") (pin "2") (pinfunction "PC13_2") (pintype "bidirectional"))
    )
    (net (code "6") (name "/BL_RX") (class "Default")
      (node (ref "D18") (pin "1") (pinfunction "IO_1") (pintype "bidirectional"))
      (node (ref "J11") (pin "2") (pinfunction "2_2") (pintype "passive"))
      (node (ref "U5") (pin "52") (pinfunction "PC11_52") (pintype "bidirectional"))
    )
    (net (code "7") (name "/BL_TX") (class "Default")
      (node (ref "D12") (pin "1") (pinfunction "IO_1") (pintype "bidirectional"))
      (node (ref "J11") (pin "3") (pinfunction "3_3") (pintype "passive"))
      (node (ref "U5") (pin "51") (pinfunction "PC10_51") (pintype "bidirectional"))
    )
    (net (code "8") (name "/BOOT0") (class "Default")
      (node (ref "U5") (pin "60") (pinfunction "BOOT0_60") (pintype "input"))
    )
    (net (code "9") (name "/CH340_CTS") (class "Default")
      (node (ref "U11") (pin "5") (pinfunction "CTS#_5") (pintype "input"))
      (node (ref "U5") (pin "45") (pinfunction "PA12_45") (pintype "bidirectional"))
    )
    (net (code "10") (name "/CH340_RTS") (class "Default")
      (node (ref "U11") (pin "4") (pinfunction "RTS#_4") (pintype "output"))
      (node (ref "U5") (pin "44") (pinfunction "PA11_44") (pintype "bidirectional"))
    )
    (net (code "11") (name "/CH340_RXD") (class "Default")
      (node (ref "U11") (pin "9") (pinfunction "RXD_9") (pintype "input"))
      (node (ref "U5") (pin "42") (pinfunction "PA9_42") (pintype "bidirectional"))
    )
    (net (code "12") (name "/CH340_TXD") (class "Default")
      (node (ref "U11") (pin "8") (pinfunction "TXD_8") (pintype "output"))
      (node (ref "U5") (pin "43") (pinfunction "PA10_43") (pintype "bidirectional"))
    )
    (net (code "13") (name "/CS1") (class "Default")
      (node (ref "R38") (pin "1") (pinfunction "1_1") (pintype "passive"))
      (node (ref "U5") (pin "38") (pinfunction "PC7_38") (pintype "bidirectional"))
      (node (ref "U7") (pin "2") (pinfunction "*CS_2") (pintype "input"))
    )
    (net (code "14") (name "/CS2") (class "Default")
      (node (ref "R39") (pin "1") (pinfunction "1_1") (pintype "passive"))
      (node (ref "U5") (pin "37") (pinfunction "PC6_37") (pintype "bidirectional"))
      (node (ref "U8") (pin "2") (pinfunction "*CS_2") (pintype "input"))
    )
    (net (code "15") (name "/CS3") (class "Default")
      (node (ref "R40") (pin "1") (pinfunction "1_1") (pintype "passive"))
      (node (ref "U5") (pin "36") (pinfunction "PB15_36") (pintype "bidirectional"))
      (node (ref "U9") (pin "2") (pinfunction "*CS_2") (pintype "input"))
    )
    (net (code "16") (name "/CS4") (class "Default")
      (node (ref "R41") (pin "1") (pinfunction "1_1") (pintype "passive"))
      (node (ref "U10") (pin "2") (pinfunction "*CS_2") (pintype "input"))
      (node (ref "U5") (pin "35") (pinfunction "PB14_35") (pintype "bidirectional"))
    )
    (net (code "17") (name "/DOUT_N") (class "Default")
      (node (ref "U11") (pin "2") (pinfunction "UD-_2") (pintype "bidirectional"))
    )
    (net (code "18") (name "/DOUT_P") (class "Default")
      (node (ref "U11") (pin "1") (pinfunction "UD+_1") (pintype "bidirectional"))
    )
    (net (code "19") (name "/ESC_PWM") (class "Default")
      (node (ref "D20") (pin "1") (pinfunction "IO_1") (pintype "bidirectional"))
      (node (ref "J13") (pin "1") (pinfunction "1_1") (pintype "passive"))
      (node (ref "U5") (pin "28") (pinfunction "PB2_28") (pintype "bidirectional"))
    )
    (net (code "20") (name "/ESC_TEL") (class "Default")
      (node (ref "D21") (pin "1") (pinfunction "IO_1") (pintype "bidirectional"))
      (node (ref "J13") (pin "2") (pinfunction "2_2") (pintype "passive"))
      (node (ref "U5") (pin "54") (pinfunction "PD2_54") (pintype "bidirectional"))
    )
    (net (code "21") (name "/LC1+") (class "Default")
      (node (ref "D23") (pin "1") (pinfunction "IO_1") (pintype "bidirectional"))
      (node (ref "J6") (pin "3") (pinfunction "3_3") (pintype "passive"))
      (node (ref "U7") (pin "11") (pinfunction "AIN0/REFP1_11") (pintype "input"))
    )
    (net (code "22") (name "/LC1-") (class "Default")
      (node (ref "D22") (pin "1") (pinfunction "IO_1") (pintype "bidirectional"))
      (node (ref "J6") (pin "4") (pinfunction "4_4") (pintype "passive"))
      (node (ref "U7") (pin "10") (pinfunction "AIN1_10") (pintype "input"))
    )
    (net (code "23") (name "/LC2+") (class "Default")
      (node (ref "D25") (pin "1") (pinfunction "IO_1") (pintype "bidirectional"))
      (node (ref "J7") (pin "3") (pinfunction "3_3") (pintype "passive"))
      (node (ref "U8") (pin "11") (pinfunction "AIN0/REFP1_11") (pintype "input"))
    )
    (net (code "24") (name "/LC2-") (class "Default")
      (node (ref "D24") (pin "1") (pinfunction "IO_1") (pintype "bidirectional"))
      (node (ref "J7") (pin "4") (pinfunction "4_4") (pintype "passive"))
      (node (ref "U8") (pin "10") (pinfunction "AIN1_10") (pintype "input"))
    )
    (net (code "25") (name "/LC3+") (class "Default")
      (node (ref "D27") (pin "1") (pinfunction "IO_1") (pintype "bidirectional"))
      (node (ref "J8") (pin "3") (pinfunction "3_3") (pintype "passive"))
      (node (ref "U9") (pin "11") (pinfunction "AIN0/REFP1_11") (pintype "input"))
    )
    (net (code "26") (name "/LC3-") (class "Default")
      (node (ref "D26") (pin "1") (pinfunction "IO_1") (pintype "bidirectional"))
      (node (ref "J8") (pin "4") (pinfunction "4_4") (pintype "passive"))
      (node (ref "U9") (pin "10") (pinfunction "AIN1_10") (pintype "input"))
    )
    (net (code "27") (name "/LC4+") (class "Default")
      (node (ref "D29") (pin "1") (pinfunction "IO_1") (pintype "bidirectional"))
      (node (ref "J9") (pin "3") (pinfunction "3_3") (pintype "passive"))
      (node (ref "U10") (pin "11") (pinfunction "AIN0/REFP1_11") (pintype "input"))
    )
    (net (code "28") (name "/LC4-") (class "Default")
      (node (ref "D28") (pin "1") (pinfunction "IO_1") (pintype "bidirectional"))
      (node (ref "J9") (pin "4") (pinfunction "4_4") (pintype "passive"))
      (node (ref "U10") (pin "10") (pinfunction "AIN1_10") (pintype "input"))
    )
    (net (code "29") (name "/MISO") (class "Default")
      (node (ref "R45") (pin "2") (pinfunction "2_2") (pintype "passive"))
      (node (ref "U10") (pin "15") (pinfunction "DOUT/*DRDY_15") (pintype "output"))
      (node (ref "U7") (pin "15") (pinfunction "DOUT/*DRDY_15") (pintype "output"))
      (node (ref "U8") (pin "15") (pinfunction "DOUT/*DRDY_15") (pintype "output"))
      (node (ref "U9") (pin "15") (pinfunction "DOUT/*DRDY_15") (pintype "output"))
    )
    (net (code "30") (name "/MOSI") (class "Default")
      (node (ref "R46") (pin "2") (pinfunction "2_2") (pintype "passive"))
      (node (ref "U10") (pin "16") (pinfunction "DIN_16") (pintype "input"))
      (node (ref "U7") (pin "16") (pinfunction "DIN_16") (pintype "input"))
      (node (ref "U8") (pin "16") (pinfunction "DIN_16") (pintype "input"))
      (node (ref "U9") (pin "16") (pinfunction "DIN_16") (pintype "input"))
    )
    (net (code "31") (name "/NRST") (class "Default")
      (node (ref "C62") (pin "2") (pinfunction "2_2") (pintype "passive"))
      (node (ref "D17") (pin "1") (pinfunction "IO_1") (pintype "bidirectional"))
      (node (ref "D2") (pin "1") (pinfunction "K_1") (pintype "passive"))
      (node (ref "J10") (pin "3") (pinfunction "3_3") (pintype "passive"))
      (node (ref "R42") (pin "1") (pinfunction "1_1") (pintype "passive"))
      (node (ref "SW1") (pin "1") (pinfunction "1_1") (pintype "passive"))
      (node (ref "U5") (pin "7") (pinfunction "~{RST}_7") (pintype "input"))
    )
    (net (code "32") (name "/OSC1_N") (class "Default")
      (node (ref "C51") (pin "1") (pinfunction "1_1") (pintype "passive"))
      (node (ref "R37") (pin "2") (pinfunction "2_2") (pintype "passive"))
      (node (ref "Y1") (pin "3") (pinfunction "OUT/IN_3") (pintype "bidirectional"))
    )
    (net (code "33") (name "/OSC1_P") (class "Default")
      (node (ref "C50") (pin "2") (pinfunction "2_2") (pintype "passive"))
      (node (ref "R36") (pin "2") (pinfunction "2_2") (pintype "passive"))
      (node (ref "Y1") (pin "1") (pinfunction "IN/OUT_1") (pintype "bidirectional"))
    )
    (net (code "34") (name "/OSC_N") (class "Default")
      (node (ref "R37") (pin "1") (pinfunction "1_1") (pintype "passive"))
      (node (ref "U5") (pin "6") (pinfunction "PH1-OSC_OUT_6") (pintype "bidirectional"))
    )
    (net (code "35") (name "/OSC_P") (class "Default")
      (node (ref "R36") (pin "1") (pinfunction "1_1") (pintype "passive"))
      (node (ref "U5") (pin "5") (pinfunction "PH0-OSC_IN_5") (pintype "bidirectional"))
    )
    (net (code "36") (name "/SCK") (class "Default")
      (node (ref "R44") (pin "2") (pinfunction "2_2") (pintype "passive"))
    )
    (net (code "37") (name "/SCL1") (class "Default")
      (node (ref "D10") (pin "1") (pinfunction "IO_1") (pintype "bidirectional"))
      (node (ref "D11") (pin "1") (pinfunction "IO_1") (pintype "bidirectional"))
      (node (ref "D9") (pin "1") (pinfunction "IO_1") (pintype "bidirectional"))
      (node (ref "J1") (pin "4") (pinfunction "4_4") (pintype "passive"))
      (node (ref "J2") (pin "4") (pinfunction "4_4") (pintype "passive"))
      (node (ref "J3") (pin "4") (pinfunction "4_4") (pintype "passive"))
      (node (ref "R14") (pin "1") (pinfunction "1_1") (pintype "passive"))
      (node (ref "U5") (pin "58") (pinfunction "PB6_58") (pintype "bidirectional"))
    )
    (net (code "38") (name "/SCL2") (class "Default")
      (node (ref "D13") (pin "1") (pinfunction "IO_1") (pintype "bidirectional"))
      (node (ref "J4") (pin "4") (pinfunction "4_4") (pintype "passive"))
      (node (ref "R16") (pin "1") (pinfunction "1_1") (pintype "passive"))
      (node (ref "U5") (pin "29") (pinfunction "PB10_29") (pintype "bidirectional"))
    )
    (net (code "39") (name "/SCL3") (class "Default")
      (node (ref "D14") (pin "1") (pinfunction "IO_1") (pintype "bidirectional"))
      (node (ref "J5") (pin "4") (pinfunction "4_4") (pintype "passive"))
      (node (ref "R18") (pin "1") (pinfunction "1_1") (pintype "passive"))
      (node (ref "U5") (pin "41") (pinfunction "PA8_41") (pintype "bidirectional"))
    )
    (net (code "40") (name "/SCLK") (class "Default")
      (node (ref "D16") (pin "1") (pinfunction "IO_1") (pintype "bidirectional"))
      (node (ref "J10") (pin "2") (pinfunction "2_2") (pintype "passive"))
      (node (ref "U10") (pin "1") (pinfunction "SCLK_1") (pintype "input"))
      (node (ref "U5") (pin "49") (pinfunction "PA14_49") (pintype "bidirectional"))
      (node (ref "U7") (pin "1") (pinfunction "SCLK_1") (pintype "input"))
      (node (ref "U8") (pin "1") (pinfunction "SCLK_1") (pintype "input"))
      (node (ref "U9") (pin "1") (pinfunction "SCLK_1") (pintype "input"))
    )
    (net (code "41") (name "/SDA1") (class "Default")
      (node (ref "D4") (pin "1") (pinfunction "IO_1") (pintype "bidirectional"))
      (node (ref "D5") (pin "1") (pinfunction "IO_1") (pintype "bidirectional"))
      (node (ref "D6") (pin "1") (pinfunction "IO_1") (pintype "bidirectional"))
      (node (ref "J1") (pin "3") (pinfunction "3_3") (pintype "passive"))
      (node (ref "J2") (pin "3") (pinfunction "3_3") (pintype "passive"))
      (node (ref "J3") (pin "3") (pinfunction "3_3") (pintype "passive"))
      (node (ref "R13") (pin "1") (pinfunction "1_1") (pintype "passive"))
      (node (ref "U5") (pin "59") (pinfunction "PB7_59") (pintype "bidirectional"))
    )
    (net (code "42") (name "/SDA2") (class "Default")
      (node (ref "D7") (pin "1") (pinfunction "IO_1") (pintype "bidirectional"))
      (node (ref "J4") (pin "3") (pinfunction "3_3") (pintype "passive"))
      (node (ref "R15") (pin "1") (pinfunction "1_1") (pintype "passive"))
      (node (ref "U5") (pin "53") (pinfunction "PC12_53") (pintype "bidirectional"))
    )
    (net (code "43") (name "/SDA3") (class "Default")
      (node (ref "D8") (pin "1") (pinfunction "IO_1") (pintype "bidirectional"))
      (node (ref "J5") (pin "3") (pinfunction "3_3") (pintype "passive"))
      (node (ref "R17") (pin "1") (pinfunction "1_1") (pintype "passive"))
      (node (ref "U5") (pin "40") (pinfunction "PC9_40") (pintype "bidirectional"))
    )
    (net (code "44") (name "/SWDIO") (class "Default")
      (node (ref "D15") (pin "1") (pinfunction "IO_1") (pintype "bidirectional"))
      (node (ref "J10") (pin "1") (pinfunction "1_1") (pintype "passive"))
      (node (ref "U5") (pin "46") (pinfunction "PA13_46") (pintype "bidirectional"))
    )
    (net (code "45") (name "GND") (class "Default")
      (node (ref "C39") (pin "2") (pinfunction "2_2") (pintype "passive"))
      (node (ref "C40") (pin "2") (pinfunction "2_2") (pintype "passive"))
      (node (ref "C41") (pin "2") (pinfunction "2_2") (pintype "passive"))
      (node (ref "C42") (pin "2") (pinfunction "2_2") (pintype "passive"))
      (node (ref "C43") (pin "2") (pinfunction "2_2") (pintype "passive"))
      (node (ref "C44") (pin "2") (pinfunction "2_2") (pintype "passive"))
      (node (ref "C45") (pin "2") (pinfunction "2_2") (pintype "passive"))
      (node (ref "C46") (pin "2") (pinfunction "2_2") (pintype "passive"))
      (node (ref "C47") (pin "2") (pinfunction "2_2") (pintype "passive"))
      (node (ref "C48") (pin "2") (pinfunction "2_2") (pintype "passive"))
      (node (ref "C50") (pin "1") (pinfunction "1_1") (pintype "passive"))
      (node (ref "C51") (pin "2") (pinfunction "2_2") (pintype "passive"))
      (node (ref "C52") (pin "2") (pinfunction "2_2") (pintype "passive"))
      (node (ref "C53") (pin "2") (pinfunction "2_2") (pintype "passive"))
      (node (ref "C54") (pin "2") (pinfunction "2_2") (pintype "passive"))
      (node (ref "C55") (pin "2") (pinfunction "2_2") (pintype "passive"))
      (node (ref "C56") (pin "2") (pinfunction "2_2") (pintype "passive"))
      (node (ref "C57") (pin "2") (pinfunction "2_2") (pintype "passive"))
      (node (ref "C58") (pin "2") (pinfunction "2_2") (pintype "passive"))
      (node (ref "C59") (pin "2") (pinfunction "2_2") (pintype "passive"))
      (node (ref "C60") (pin "2") (pinfunction "2_2") (pintype "passive"))
      (node (ref "C61") (pin "2") (pinfunction "2_2") (pintype "passive"))
      (node (ref "C62") (pin "1") (pinfunction "1_1") (pintype "passive"))
      (node (ref "C63") (pin "1") (pinfunction "1_1") (pintype "passive"))
      (node (ref "C64") (pin "2") (pinfunction "2_2") (pintype "passive"))
      (node (ref "C65") (pin "2") (pinfunction "2_2") (pintype "passive"))
      (node (ref "C66") (pin "2") (pinfunction "2_2") (pintype "passive"))
      (node (ref "C67") (pin "2") (pinfunction "2_2") (pintype "passive"))
      (node (ref "C68") (pin "2") (pinfunction "2_2") (pintype "passive"))
      (node (ref "C69") (pin "2") (pinfunction "2_2") (pintype "passive"))
      (node (ref "C70") (pin "2") (pinfunction "2_2") (pintype "passive"))
      (node (ref "C71") (pin "2") (pinfunction "2_2") (pintype "passive"))
      (node (ref "C72") (pin "2") (pinfunction "2_2") (pintype "passive"))
      (node (ref "C73") (pin "2") (pinfunction "2_2") (pintype "passive"))
      (node (ref "D10") (pin "2") (pinfunction "GND_2") (pintype "power_in"))
      (node (ref "D11") (pin "2") (pinfunction "GND_2") (pintype "power_in"))
      (node (ref "D12") (pin "2") (pinfunction "GND_2") (pintype "power_in"))
      (node (ref "D13") (pin "2") (pinfunction "GND_2") (pintype "power_in"))
      (node (ref "D14") (pin "2") (pinfunction "GND_2") (pintype "power_in"))
      (node (ref "D15") (pin "2") (pinfunction "GND_2") (pintype "power_in"))
      (node (ref "D16") (pin "2") (pinfunction "GND_2") (pintype "power_in"))
      (node (ref "D17") (pin "2") (pinfunction "GND_2") (pintype "power_in"))
      (node (ref "D18") (pin "2") (pinfunction "GND_2") (pintype "power_in"))
      (node (ref "D19") (pin "2") (pinfunction "GND_2") (pintype "power_in"))
      (node (ref "D20") (pin "2") (pinfunction "GND_2") (pintype "power_in"))
      (node (ref "D21") (pin "2") (pinfunction "GND_2") (pintype "power_in"))
      (node (ref "D22") (pin "2") (pinfunction "GND_2") (pintype "power_in"))
      (node (ref "D23") (pin "2") (pinfunction "GND_2") (pintype "power_in"))
      (node (ref "D24") (pin "2") (pinfunction "GND_2") (pintype "power_in"))
      (node (ref "D25") (pin "2") (pinfunction "GND_2") (pintype "power_in"))
      (node (ref "D26") (pin "2") (pinfunction "GND_2") (pintype "power_in"))
      (node (ref "D27") (pin "2") (pinfunction "GND_2") (pintype "power_in"))
      (node (ref "D28") (pin "2") (pinfunction "GND_2") (pintype "power_in"))
      (node (ref "D29") (pin "2") (pinfunction "GND_2") (pintype "power_in"))
      (node (ref "D4") (pin "2") (pinfunction "GND_2") (pintype "power_in"))
      (node (ref "D5") (pin "2") (pinfunction "GND_2") (pintype "power_in"))
      (node (ref "D6") (pin "2") (pinfunction "GND_2") (pintype "power_in"))
      (node (ref "D7") (pin "2") (pinfunction "GND_2") (pintype "power_in"))
      (node (ref "D8") (pin "2") (pinfunction "GND_2") (pintype "power_in"))
      (node (ref "D9") (pin "2") (pinfunction "GND_2") (pintype "power_in"))
      (node (ref "J1") (pin "2") (pinfunction "2_2") (pintype "passive"))
      (node (ref "J1") (pin "5") (pinfunction "MNT_1_5") (pintype "passive"))
      (node (ref "J1") (pin "6") (pinfunction "MNT_2_6") (pintype "passive"))
      (node (ref "J10") (pin "5") (pinfunction "5_5") (pintype "passive"))
      (node (ref "J11") (pin "5") (pinfunction "5_5") (pintype "passive"))
      (node (ref "J11") (pin "6") (pinfunction "MNT_1_6") (pintype "passive"))
      (node (ref "J11") (pin "7") (pinfunction "MNT_2_7") (pintype "passive"))
      (node (ref "J13") (pin "3") (pinfunction "3_3") (pintype "passive"))
      (node (ref "J13") (pin "4") (pinfunction "MNT_1_4") (pintype "passive"))
      (node (ref "J13") (pin "5") (pinfunction "MNT_2_5") (pintype "passive"))
      (node (ref "J2") (pin "2") (pinfunction "2_2") (pintype "passive"))
      (node (ref "J2") (pin "5") (pinfunction "MNT_1_5") (pintype "passive"))
      (node (ref "J2") (pin "6") (pinfunction "MNT_2_6") (pintype "passive"))
      (node (ref "J3") (pin "2") (pinfunction "2_2") (pintype "passive"))
      (node (ref "J3") (pin "5") (pinfunction "MNT_1_5") (pintype "passive"))
      (node (ref "J3") (pin "6") (pinfunction "MNT_2_6") (pintype "passive"))
      (node (ref "J4") (pin "2") (pinfunction "2_2") (pintype "passive"))
      (node (ref "J4") (pin "5") (pinfunction "MNT_1_5") (pintype "passive"))
      (node (ref "J4") (pin "6") (pinfunction "MNT_2_6") (pintype "passive"))
      (node (ref "J5") (pin "2") (pinfunction "2_2") (pintype "passive"))
      (node (ref "J5") (pin "5") (pinfunction "MNT_1_5") (pintype "passive"))
      (node (ref "J5") (pin "6") (pinfunction "MNT_2_6") (pintype "passive"))
      (node (ref "J6") (pin "2") (pinfunction "2_2") (pintype "passive"))
      (node (ref "J6") (pin "5") (pinfunction "MNT_1_5") (pintype "passive"))
      (node (ref "J6") (pin "6") (pinfunction "MNT_2_6") (pintype "passive"))
      (node (ref "J7") (pin "2") (pinfunction "2_2") (pintype "passive"))
      (node (ref "J7") (pin "5") (pinfunction "MNT_1_5") (pintype "passive"))
      (node (ref "J7") (pin "6") (pinfunction "MNT_2_6") (pintype "passive"))
      (node (ref "J8") (pin "2") (pinfunction "2_2") (pintype "passive"))
      (node (ref "J8") (pin "5") (pinfunction "MNT_1_5") (pintype "passive"))
      (node (ref "J8") (pin "6") (pinfunction "MNT_2_6") (pintype "passive"))
      (node (ref "J9") (pin "2") (pinfunction "2_2") (pintype "passive"))
      (node (ref "J9") (pin "5") (pinfunction "MNT_1_5") (pintype "passive"))
      (node (ref "J9") (pin "6") (pinfunction "MNT_2_6") (pintype "passive"))
      (node (ref "SW1") (pin "2") (pinfunction "2_2") (pintype "passive"))
      (node (ref "U10") (pin "3") (pinfunction "CLK_3") (pintype "input"))
      (node (ref "U10") (pin "4") (pinfunction "DGND_4") (pintype "power_in"))
      (node (ref "U10") (pin "5") (pinfunction "AVSS_5") (pintype "power_in"))
      (node (ref "U10") (pin "8") (pinfunction "REFN0_8") (pintype "input"))
      (node (ref "U11") (pin "3") (pinfunction "GND_3") (pintype "power_in"))
      (node (ref "U5") (pin "12") (pinfunction "VSSA/VREF-_12") (pintype "power_in"))
      (node (ref "U5") (pin "18") (pinfunction "VSS_18") (pintype "power_in"))
      (node (ref "U5") (pin "31") (pinfunction "VSS_31") (pintype "power_in"))
      (node (ref "U5") (pin "47") (pinfunction "VSS_47") (pintype "power_in"))
      (node (ref "U5") (pin "63") (pinfunction "VSS_63") (pintype "power_in"))
      (node (ref "U7") (pin "3") (pinfunction "CLK_3") (pintype "input"))
      (node (ref "U7") (pin "4") (pinfunction "DGND_4") (pintype "power_in"))
      (node (ref "U7") (pin "5") (pinfunction "AVSS_5") (pintype "power_in"))
      (node (ref "U7") (pin "8") (pinfunction "REFN0_8") (pintype "input"))
      (node (ref "U8") (pin "3") (pinfunction "CLK_3") (pintype "input"))
      (node (ref "U8") (pin "4") (pinfunction "DGND_4") (pintype "power_in"))
      (node (ref "U8") (pin "5") (pinfunction "AVSS_5") (pintype "power_in"))
      (node (ref "U8") (pin "8") (pinfunction "REFN0_8") (pintype "input"))
      (node (ref "U9") (pin "3") (pinfunction "CLK_3") (pintype "input"))
      (node (ref "U9") (pin "4") (pinfunction "DGND_4") (pintype "power_in"))
      (node (ref "U9") (pin "5") (pinfunction "AVSS_5") (pintype "power_in"))
      (node (ref "U9") (pin "8") (pinfunction "REFN0_8") (pintype "input"))
      (node (ref "Y1") (pin "2") (pinfunction "GND_2") (pintype "power_in"))
      (node (ref "Y1") (pin "4") (pinfunction "GND_4") (pintype "power_in"))
    )
    (net (code "46") (name "Net-(D2-A)") (class "Default")
      (node (ref "D2") (pin "2") (pinfunction "A_2") (pintype "passive"))
      (node (ref "R43") (pin "2") (pinfunction "2_2") (pintype "passive"))
    )
    (net (code "47") (name "Net-(U5A-PA5)") (class "Default")
      (node (ref "R44") (pin "1") (pinfunction "1_1") (pintype "passive"))
      (node (ref "U5") (pin "21") (pinfunction "PA5_21") (pintype "bidirectional"))
    )
    (net (code "48") (name "Net-(U5A-PA6)") (class "Default")
      (node (ref "R45") (pin "1") (pinfunction "1_1") (pintype "passive"))
      (node (ref "U5") (pin "22") (pinfunction "PA6_22") (pintype "bidirectional"))
    )
    (net (code "49") (name "Net-(U5A-PA7)") (class "Default")
      (node (ref "R46") (pin "1") (pinfunction "1_1") (pintype "passive"))
      (node (ref "U5") (pin "23") (pinfunction "PA7_23") (pintype "bidirectional"))
    )
    (net (code "50") (name "Net-(U5B-VCAP_1)") (class "Default")
      (node (ref "C48") (pin "1") (pinfunction "1_1") (pintype "passive"))
      (node (ref "U5") (pin "30") (pinfunction "VCAP_1_30") (pintype "power_in"))
    )
    (net (code "51") (name "unconnected-(U5A-PA0-Pad14)") (class "Default")
      (node (ref "U5") (pin "14") (pinfunction "PA0_14") (pintype "bidirectional"))
    )
    (net (code "52") (name "unconnected-(U5A-PA1-Pad15)") (class "Default")
      (node (ref "U5") (pin "15") (pinfunction "PA1_15") (pintype "bidirectional"))
    )
    (net (code "53") (name "unconnected-(U5A-PA2-Pad16)") (class "Default")
      (node (ref "U5") (pin "16") (pinfunction "PA2_16") (pintype "bidirectional"))
    )
    (net (code "54") (name "unconnected-(U5A-PA3-Pad17)") (class "Default")
      (node (ref "U5") (pin "17") (pinfunction "PA3_17") (pintype "bidirectional"))
    )
    (net (code "55") (name "unconnected-(U5A-PA4-Pad20)") (class "Default")
      (node (ref "U5") (pin "20") (pinfunction "PA4_20") (pintype "bidirectional"))
    )
    (net (code "56") (name "unconnected-(U5A-PA15-Pad50)") (class "Default")
      (node (ref "U5") (pin "50") (pinfunction "PA15_50") (pintype "bidirectional"))
    )
    (net (code "57") (name "unconnected-(U5A-PB0-Pad26)") (class "Default")
      (node (ref "U5") (pin "26") (pinfunction "PB0_26") (pintype "bidirectional"))
    )
    (net (code "58") (name "unconnected-(U5A-PB1-Pad27)") (class "Default")
      (node (ref "U5") (pin "27") (pinfunction "PB1_27") (pintype "bidirectional"))
    )
    (net (code "59") (name "unconnected-(U5A-PB3-Pad55)") (class "Default")
      (node (ref "U5") (pin "55") (pinfunction "PB3_55") (pintype "bidirectional"))
    )
    (net (code "60") (name "unconnected-(U5A-PB4-Pad56)") (class "Default")
      (node (ref "U5") (pin "56") (pinfunction "PB4_56") (pintype "bidirectional"))
    )
    (net (code "61") (name "unconnected-(U5A-PB5-Pad57)") (class "Default")
      (node (ref "U5") (pin "57") (pinfunction "PB5_57") (pintype "bidirectional"))
    )
    (net (code "62") (name "unconnected-(U5A-PB8-Pad61)") (class "Default")
      (node (ref "U5") (pin "61") (pinfunction "PB8_61") (pintype "bidirectional"))
    )
    (net (code "63") (name "unconnected-(U5A-PB9-Pad62)") (class "Default")
      (node (ref "U5") (pin "62") (pinfunction "PB9_62") (pintype "bidirectional"))
    )
    (net (code "64") (name "unconnected-(U5A-PB12-Pad33)") (class "Default")
      (node (ref "U5") (pin "33") (pinfunction "PB12_33") (pintype "bidirectional"))
    )
    (net (code "65") (name "unconnected-(U5A-PB13-Pad34)") (class "Default")
      (node (ref "U5") (pin "34") (pinfunction "PB13_34") (pintype "bidirectional"))
    )
    (net (code "66") (name "unconnected-(U5A-PC0-Pad8)") (class "Default")
      (node (ref "U5") (pin "8") (pinfunction "PC0_8") (pintype "bidirectional"))
    )
    (net (code "67") (name "unconnected-(U5A-PC3-Pad11)") (class "Default")
      (node (ref "U5") (pin "11") (pinfunction "PC3_11") (pintype "bidirectional"))
    )
    (net (code "68") (name "unconnected-(U5A-PC4-Pad24)") (class "Default")
      (node (ref "U5") (pin "24") (pinfunction "PC4_24") (pintype "bidirectional"))
    )
    (net (code "69") (name "unconnected-(U5A-PC5-Pad25)") (class "Default")
      (node (ref "U5") (pin "25") (pinfunction "PC5_25") (pintype "bidirectional"))
    )
    (net (code "70") (name "unconnected-(U5A-PC8-Pad39)") (class "Default")
      (node (ref "U5") (pin "39") (pinfunction "PC8_39") (pintype "bidirectional"))
    )
    (net (code "71") (name "unconnected-(U5A-PC14-OSC32_IN-Pad3)") (class "Default")
      (node (ref "U5") (pin "3") (pinfunction "PC14-OSC32_IN_3") (pintype "bidirectional+no_connect"))
    )
    (net (code "72") (name "unconnected-(U5A-PC15-OSC32_OUT-Pad4)") (class "Default")
      (node (ref "U5") (pin "4") (pinfunction "PC15-OSC32_OUT_4") (pintype "bidirectional+no_connect"))
    )
    (net (code "73") (name "unconnected-(U7-*DRDY-Pad14)") (class "Default")
      (node (ref "U7") (pin "14") (pinfunction "*DRDY_14") (pintype "output+no_connect"))
    )
    (net (code "74") (name "unconnected-(U7-AIN2-Pad7)") (class "Default")
      (node (ref "U7") (pin "7") (pinfunction "AIN2_7") (pintype "input+no_connect"))
    )
    (net (code "75") (name "unconnected-(U7-AIN3{slash}REFN1-Pad6)") (class "Default")
      (node (ref "U7") (pin "6") (pinfunction "AIN3/REFN1_6") (pintype "input+no_connect"))
    )
    (net (code "76") (name "unconnected-(U8-*DRDY-Pad14)") (class "Default")
      (node (ref "U8") (pin "14") (pinfunction "*DRDY_14") (pintype "output+no_connect"))
    )
    (net (code "77") (name "unconnected-(U8-AIN2-Pad7)") (class "Default")
      (node (ref "U8") (pin "7") (pinfunction "AIN2_7") (pintype "input+no_connect"))
    )
    (net (code "78") (name "unconnected-(U8-AIN3{slash}REFN1-Pad6)") (class "Default")
      (node (ref "U8") (pin "6") (pinfunction "AIN3/REFN1_6") (pintype "input+no_connect"))
    )
    (net (code "79") (name "unconnected-(U9-*DRDY-Pad14)") (class "Default")
      (node (ref "U9") (pin "14") (pinfunction "*DRDY_14") (pintype "output+no_connect"))
    )
    (net (code "80") (name "unconnected-(U9-AIN2-Pad7)") (class "Default")
      (node (ref "U9") (pin "7") (pinfunction "AIN2_7") (pintype "input+no_connect"))
    )
    (net (code "81") (name "unconnected-(U9-AIN3{slash}REFN1-Pad6)") (class "Default")
      (node (ref "U9") (pin "6") (pinfunction "AIN3/REFN1_6") (pintype "input+no_connect"))
    )
    (net (code "82") (name "unconnected-(U10-*DRDY-Pad14)") (class "Default")
      (node (ref "U10") (pin "14") (pinfunction "*DRDY_14") (pintype "output+no_connect"))
    )
    (net (code "83") (name "unconnected-(U10-AIN2-Pad7)") (class "Default")
      (node (ref "U10") (pin "7") (pinfunction "AIN2_7") (pintype "input+no_connect"))
    )
    (net (code "84") (name "unconnected-(U10-AIN3{slash}REFN1-Pad6)") (class "Default")
      (node (ref "U10") (pin "6") (pinfunction "AIN3/REFN1_6") (pintype "input+no_connect"))
    )
    (net (code "85") (name "unconnected-(U11-TNOW-Pad6)") (class "Default")
      (node (ref "U11") (pin "6") (pinfunction "TNOW_6") (pintype "output+no_connect"))
    )
  )
)
